# Bidirectional_Logic_Converter.net
KiCad netlist of a schematic drawn in EAGLE
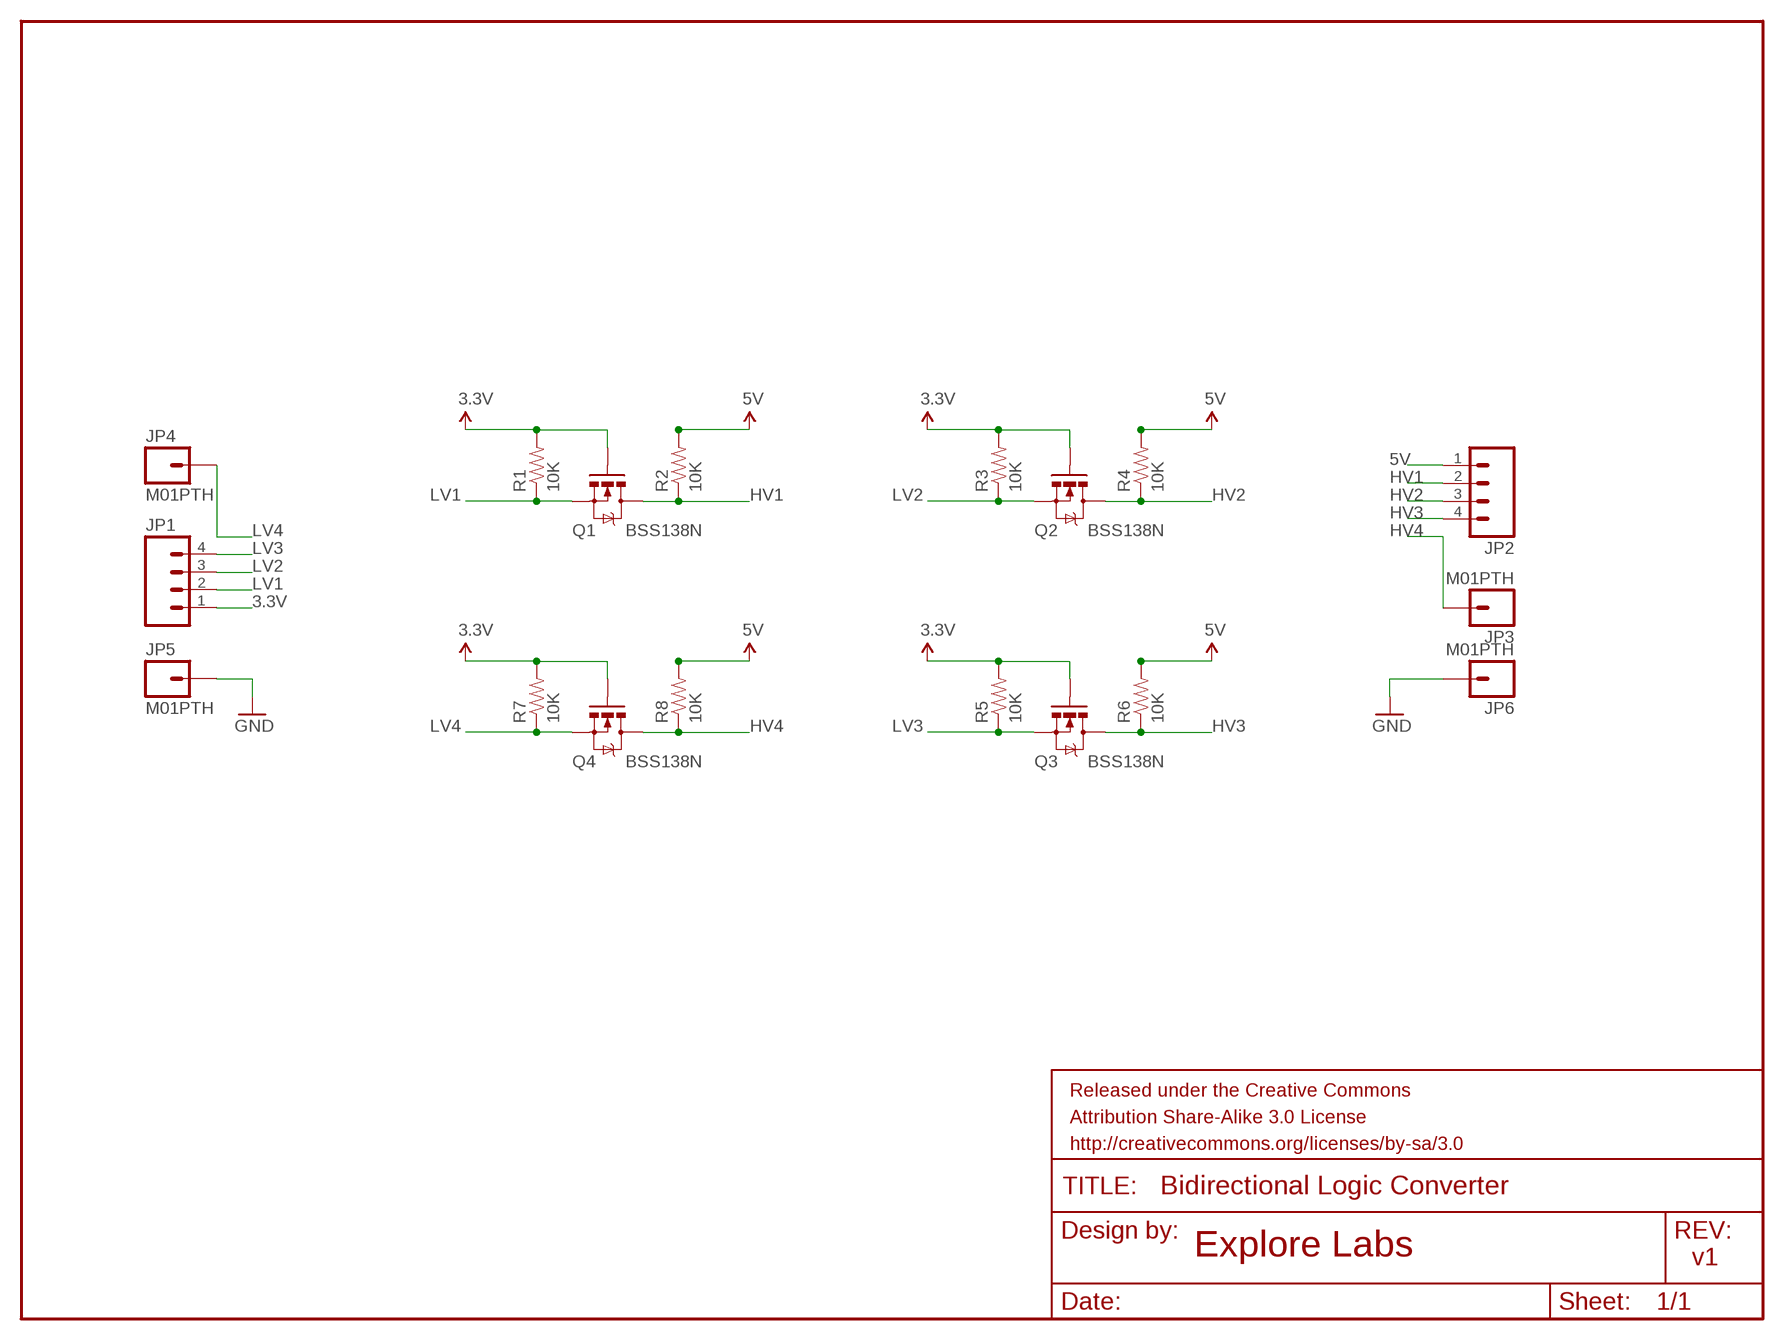
[diagram p0: schematic, sheet 1]

(export (version "E")
  (design (tool "Eeschema 10.0.6"))
  (components
    (comp (ref "JP1")
      (value "M04PTH")
      (footprint "eagle-import:1X04")
      (libsource (lib "eagle-import") (part "M04PTH"))
    )
    (comp (ref "JP2")
      (value "M04PTH")
      (footprint "eagle-import:1X04")
      (libsource (lib "eagle-import") (part "M04PTH"))
    )
    (comp (ref "JP3")
      (value "M01PTH")
      (footprint "eagle-import:1X01")
      (libsource (lib "eagle-import") (part "M01PTH"))
    )
    (comp (ref "JP4")
      (value "M01PTH")
      (footprint "eagle-import:1X01")
      (libsource (lib "eagle-import") (part "M01PTH"))
    )
    (comp (ref "JP5")
      (value "M01PTH")
      (footprint "eagle-import:1X01")
      (libsource (lib "eagle-import") (part "M01PTH"))
    )
    (comp (ref "JP6")
      (value "M01PTH")
      (footprint "eagle-import:1X01")
      (libsource (lib "eagle-import") (part "M01PTH"))
    )
    (comp (ref "Q1")
      (value "BSS138N")
      (footprint "eagle-import:SOT23-3")
      (libsource (lib "eagle-import") (part "MOSFET-NCHANNELSMD"))
    )
    (comp (ref "Q2")
      (value "BSS138N")
      (footprint "eagle-import:SOT23-3")
      (libsource (lib "eagle-import") (part "MOSFET-NCHANNELSMD"))
    )
    (comp (ref "Q3")
      (value "BSS138N")
      (footprint "eagle-import:SOT23-3")
      (libsource (lib "eagle-import") (part "MOSFET-NCHANNELSMD"))
    )
    (comp (ref "Q4")
      (value "BSS138N")
      (footprint "eagle-import:SOT23-3")
      (libsource (lib "eagle-import") (part "MOSFET-NCHANNELSMD"))
    )
    (comp (ref "R1")
      (value "10K")
      (footprint "eagle-import:0603-RES")
      (libsource (lib "eagle-import") (part "RESISTOR0603-RES"))
    )
    (comp (ref "R2")
      (value "10K")
      (footprint "eagle-import:0603-RES")
      (libsource (lib "eagle-import") (part "RESISTOR0603-RES"))
    )
    (comp (ref "R3")
      (value "10K")
      (footprint "eagle-import:0603-RES")
      (libsource (lib "eagle-import") (part "RESISTOR0603-RES"))
    )
    (comp (ref "R4")
      (value "10K")
      (footprint "eagle-import:0603-RES")
      (libsource (lib "eagle-import") (part "RESISTOR0603-RES"))
    )
    (comp (ref "R5")
      (value "10K")
      (footprint "eagle-import:0603-RES")
      (libsource (lib "eagle-import") (part "RESISTOR0603-RES"))
    )
    (comp (ref "R6")
      (value "10K")
      (footprint "eagle-import:0603-RES")
      (libsource (lib "eagle-import") (part "RESISTOR0603-RES"))
    )
    (comp (ref "R7")
      (value "10K")
      (footprint "eagle-import:0603-RES")
      (libsource (lib "eagle-import") (part "RESISTOR0603-RES"))
    )
    (comp (ref "R8")
      (value "10K")
      (footprint "eagle-import:0603-RES")
      (libsource (lib "eagle-import") (part "RESISTOR0603-RES"))
    )
  )
  (nets
    (net (code "1") (name "/HV1") (class "Default")
      (node (ref "JP2") (pin "2") (pinfunction "2_2") (pintype "passive"))
      (node (ref "Q1") (pin "3") (pinfunction "D_3") (pintype "passive"))
      (node (ref "R2") (pin "1") (pinfunction "1_1") (pintype "passive"))
    )
    (net (code "2") (name "/HV2") (class "Default")
      (node (ref "JP2") (pin "3") (pinfunction "3_3") (pintype "passive"))
      (node (ref "Q2") (pin "3") (pinfunction "D_3") (pintype "passive"))
      (node (ref "R4") (pin "1") (pinfunction "1_1") (pintype "passive"))
    )
    (net (code "3") (name "/HV3") (class "Default")
      (node (ref "JP2") (pin "4") (pinfunction "4_4") (pintype "passive"))
      (node (ref "Q3") (pin "3") (pinfunction "D_3") (pintype "passive"))
      (node (ref "R6") (pin "1") (pinfunction "1_1") (pintype "passive"))
    )
    (net (code "4") (name "/HV4") (class "Default")
      (node (ref "JP3") (pin "1") (pinfunction "1_1") (pintype "passive"))
      (node (ref "Q4") (pin "3") (pinfunction "D_3") (pintype "passive"))
      (node (ref "R8") (pin "1") (pinfunction "1_1") (pintype "passive"))
    )
    (net (code "5") (name "/LV1") (class "Default")
      (node (ref "JP1") (pin "2") (pinfunction "2_2") (pintype "passive"))
      (node (ref "Q1") (pin "2") (pinfunction "S_2") (pintype "passive"))
      (node (ref "R1") (pin "1") (pinfunction "1_1") (pintype "passive"))
    )
    (net (code "6") (name "/LV2") (class "Default")
      (node (ref "JP1") (pin "3") (pinfunction "3_3") (pintype "passive"))
      (node (ref "Q2") (pin "2") (pinfunction "S_2") (pintype "passive"))
      (node (ref "R3") (pin "1") (pinfunction "1_1") (pintype "passive"))
    )
    (net (code "7") (name "/LV3") (class "Default")
      (node (ref "JP1") (pin "4") (pinfunction "4_4") (pintype "passive"))
      (node (ref "Q3") (pin "2") (pinfunction "S_2") (pintype "passive"))
      (node (ref "R5") (pin "1") (pinfunction "1_1") (pintype "passive"))
    )
    (net (code "8") (name "/LV4") (class "Default")
      (node (ref "JP4") (pin "1") (pinfunction "1_1") (pintype "passive"))
      (node (ref "Q4") (pin "2") (pinfunction "S_2") (pintype "passive"))
      (node (ref "R7") (pin "1") (pinfunction "1_1") (pintype "passive"))
    )
    (net (code "9") (name "3.3V") (class "Default")
      (node (ref "JP1") (pin "1") (pinfunction "1_1") (pintype "passive"))
      (node (ref "Q1") (pin "1") (pinfunction "G_1") (pintype "passive"))
      (node (ref "Q2") (pin "1") (pinfunction "G_1") (pintype "passive"))
      (node (ref "Q3") (pin "1") (pinfunction "G_1") (pintype "passive"))
      (node (ref "Q4") (pin "1") (pinfunction "G_1") (pintype "passive"))
      (node (ref "R1") (pin "2") (pinfunction "2_2") (pintype "passive"))
      (node (ref "R3") (pin "2") (pinfunction "2_2") (pintype "passive"))
      (node (ref "R5") (pin "2") (pinfunction "2_2") (pintype "passive"))
      (node (ref "R7") (pin "2") (pinfunction "2_2") (pintype "passive"))
    )
    (net (code "10") (name "5V") (class "Default")
      (node (ref "JP2") (pin "1") (pinfunction "1_1") (pintype "passive"))
      (node (ref "R2") (pin "2") (pinfunction "2_2") (pintype "passive"))
      (node (ref "R4") (pin "2") (pinfunction "2_2") (pintype "passive"))
      (node (ref "R6") (pin "2") (pinfunction "2_2") (pintype "passive"))
      (node (ref "R8") (pin "2") (pinfunction "2_2") (pintype "passive"))
    )
    (net (code "11") (name "GND") (class "Default")
      (node (ref "JP5") (pin "1") (pinfunction "1_1") (pintype "passive"))
      (node (ref "JP6") (pin "1") (pinfunction "1_1") (pintype "passive"))
    )
  )
)
